# SCH_HV-Switch_2025-05-17.net
KiCad netlist of a schematic drawn in EasyEDA
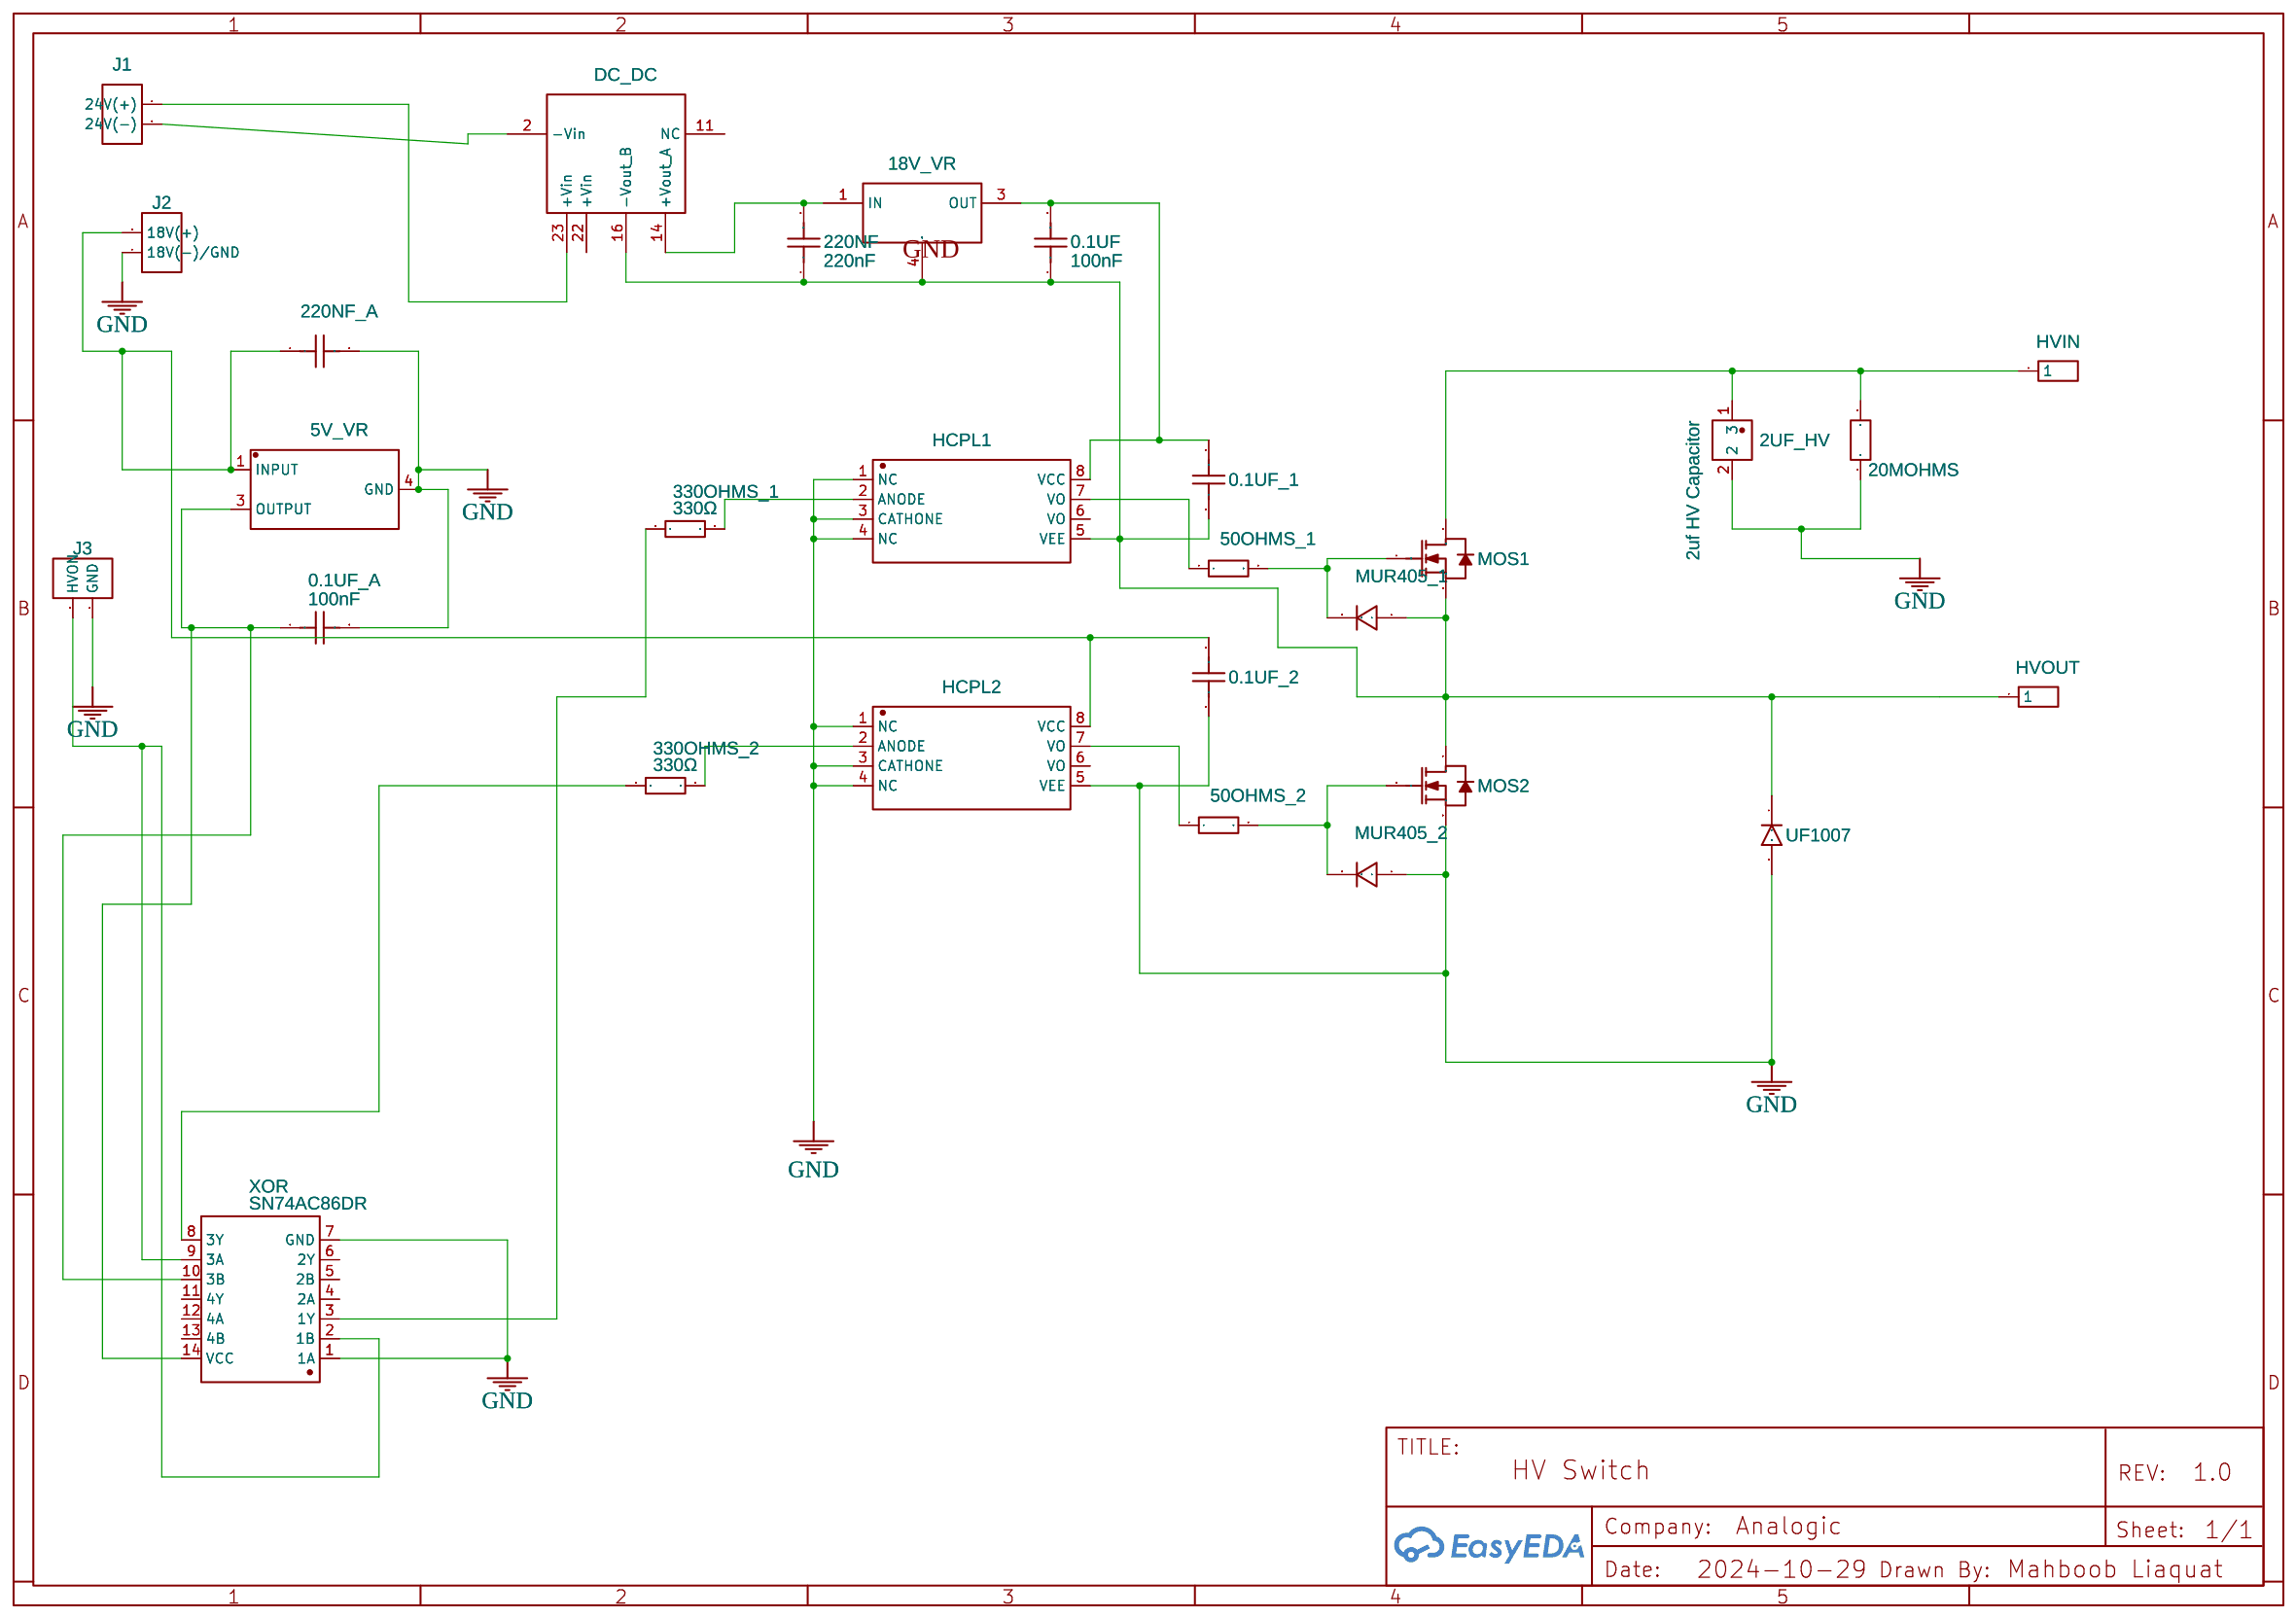
[diagram p0: schematic sheet]

(export (version "E")
  (design (tool "Eeschema 10.0.6"))
  (components
    (comp (ref "0.1UF")
      (value "100nF")
      (fields (field (name "Manufacturer Part") "C2012X7T2E104K125AE") (field (name "Manufacturer") "TDK"))
      (libsource (lib "") (part "C2012X7T2E104K125AE"))
    )
    (comp (ref "0.1UF_1")
      (value "100nF")
      (fields (field (name "Manufacturer Part") "C2012X7T2E104K125AE") (field (name "Manufacturer") "TDK"))
      (libsource (lib "") (part "C2012X7T2E104K125AE_3"))
    )
    (comp (ref "0.1UF_2")
      (value "100nF")
      (fields (field (name "Manufacturer Part") "C2012X7T2E104K125AE") (field (name "Manufacturer") "TDK"))
      (libsource (lib "") (part "C2012X7T2E104K125AE_2"))
    )
    (comp (ref "0.1UF_A")
      (value "100nF")
      (fields (field (name "Manufacturer Part") "C2012X7T2E104K125AE") (field (name "Manufacturer") "TDK"))
      (libsource (lib "") (part "C2012X7T2E104K125AE_1"))
    )
    (comp (ref "2UF_HV") (value "2uf HV Capacitor") (libsource (lib "") (part "2uf HV Capacitor")))
    (comp (ref "5V_VR")
      (value "MC7805BDTG")
      (fields (field (name "Manufacturer") "onsemi(安森美)"))
      (libsource (lib "") (part "MC7805BDTG"))
    )
    (comp (ref "18V_VR")
      (value "MC7818CD2TR4G")
      (fields (field (name "Manufacturer") "onsemi(安森美)"))
      (libsource (lib "") (part "MC7818CD2TR4G"))
    )
    (comp (ref "20MOHMS")
      (value "3.32MΩ")
      (fields
        (field (name "Manufacturer Part") "CRMA2010AF3M32FKEF")
        (field (name "Manufacturer") "VISHAY(威世)")
      )
      (libsource (lib "") (part "CRMA2010AF3M32FKEF"))
    )
    (comp (ref "50OHMS_1")
      (value "49.9Ω")
      (fields (field (name "Manufacturer Part") "RC1206FR-0749R9L") (field (name "Manufacturer") "YAGEO(国巨)"))
      (libsource (lib "") (part "RC1206FR-0749R9L"))
    )
    (comp (ref "50OHMS_2")
      (value "49.9Ω")
      (fields (field (name "Manufacturer Part") "RC1206FR-0749R9L") (field (name "Manufacturer") "YAGEO(国巨)"))
      (libsource (lib "") (part "RC1206FR-0749R9L"))
    )
    (comp (ref "220NF")
      (value "220nF")
      (fields
        (field (name "Manufacturer Part") "CC1206JKX7R9BB224")
        (field (name "Manufacturer") "YAGEO(国巨)")
      )
      (libsource (lib "") (part "CC1206JKX7R9BB224_1"))
    )
    (comp (ref "220NF_A")
      (value "220nF")
      (fields
        (field (name "Manufacturer Part") "CC1206JKX7R9BB224")
        (field (name "Manufacturer") "YAGEO(国巨)")
      )
      (libsource (lib "") (part "CC1206JKX7R9BB224"))
    )
    (comp (ref "330OHMS_1")
      (value "330Ω")
      (fields (field (name "Manufacturer Part") "RC0603JR-07330RL") (field (name "Manufacturer") "YAGEO(国巨)"))
      (libsource (lib "") (part "RC0603JR-07330RL"))
    )
    (comp (ref "330OHMS_2")
      (value "330Ω")
      (fields (field (name "Manufacturer Part") "RC0603JR-07330RL") (field (name "Manufacturer") "YAGEO(国巨)"))
      (libsource (lib "") (part "RC0603JR-07330RL"))
    )
    (comp (ref "DC_DC") (value "DC DC converter") (libsource (lib "") (part "DC DC converter")))
    (comp (ref "HCPL1")
      (value "HCPL-3120-300E")
      (fields (field (name "Manufacturer") "Broadcom/AVAGO(安华高)"))
      (libsource (lib "") (part "HCPL-3120-300E"))
    )
    (comp (ref "HCPL2")
      (value "HCPL-3120-300E")
      (fields (field (name "Manufacturer") "Broadcom/AVAGO(安华高)"))
      (libsource (lib "") (part "HCPL-3120-300E"))
    )
    (comp (ref "HVIN") (value "HVIN") (libsource (lib "") (part "HDR-M-2.54_1x1_1")))
    (comp (ref "HVOUT") (value "HVOUT") (libsource (lib "") (part "HDR-M-2.54_1x1")))
    (comp (ref "J1")
      (value "282836-2")
      (fields (field (name "Manufacturer") "TE-Connectivity"))
      (libsource (lib "") (part "282836-2_1"))
    )
    (comp (ref "J2")
      (value "282836-2")
      (fields (field (name "Manufacturer") "TE-Connectivity"))
      (libsource (lib "") (part "282836-2"))
    )
    (comp (ref "J3")
      (value "282836-2")
      (fields (field (name "Manufacturer") "TE-Connectivity"))
      (libsource (lib "") (part "282836-2_2"))
    )
    (comp (ref "MOS1")
      (value "IXTA1N200P3HV")
      (fields (field (name "Manufacturer") "Littelfuse/IXYS"))
      (libsource (lib "") (part "IXTA1N200P3HV"))
    )
    (comp (ref "MOS2")
      (value "IXTA1N200P3HV")
      (fields (field (name "Manufacturer") "Littelfuse/IXYS"))
      (libsource (lib "") (part "IXTA1N200P3HV"))
    )
    (comp (ref "MUR405_1")
      (value "MURS105T3G")
      (fields (field (name "Manufacturer") "onsemi(安森美)"))
      (libsource (lib "") (part "MURS105T3G"))
    )
    (comp (ref "MUR405_2")
      (value "MURS105T3G")
      (fields (field (name "Manufacturer") "onsemi(安森美)"))
      (libsource (lib "") (part "MURS105T3G"))
    )
    (comp (ref "UF1007")
      (value "US1M-13-F")
      (fields (field (name "Manufacturer") "DIODES(美台)"))
      (libsource (lib "") (part "US1M-13-F"))
    )
    (comp (ref "XOR")
      (value "SN74AC86DR")
      (fields (field (name "Manufacturer") "TI(德州仪器)"))
      (libsource (lib "") (part "SN74AC86DR"))
    )
  )
  (nets
    (net (code "1") (name "GND") (class "Default")
      (node (ref "0.1UF_2") (pin "1") (pinfunction "1_1") (pintype "unspecified"))
      (node (ref "0.1UF_A") (pin "2") (pinfunction "2_2") (pintype "unspecified"))
      (node (ref "20MOHMS") (pin "1") (pinfunction "1_1") (pintype "unspecified"))
      (node (ref "220NF_A") (pin "2") (pinfunction "2_2") (pintype "unspecified"))
      (node (ref "2UF_HV") (pin "2") (pinfunction "2_2") (pintype "unspecified"))
      (node (ref "5V_VR") (pin "4") (pinfunction "GND_4") (pintype "unspecified"))
      (node (ref "HCPL1") (pin "1") (pinfunction "NC_1") (pintype "unspecified"))
      (node (ref "HCPL1") (pin "3") (pinfunction "CATHONE_3") (pintype "unspecified"))
      (node (ref "HCPL1") (pin "4") (pinfunction "NC_4") (pintype "unspecified"))
      (node (ref "HCPL2") (pin "1") (pinfunction "NC_1") (pintype "unspecified"))
      (node (ref "HCPL2") (pin "3") (pinfunction "CATHONE_3") (pintype "unspecified"))
      (node (ref "HCPL2") (pin "4") (pinfunction "NC_4") (pintype "unspecified"))
      (node (ref "HCPL2") (pin "5") (pinfunction "VEE_5") (pintype "unspecified"))
      (node (ref "J2") (pin "1") (pinfunction "18V(-)/GND_1") (pintype "unspecified"))
      (node (ref "J3") (pin "1") (pinfunction "GND_1") (pintype "unspecified"))
      (node (ref "MOS2") (pin "3") (pinfunction "S_3") (pintype "unspecified"))
      (node (ref "MUR405_2") (pin "1") (pinfunction "1_1") (pintype "unspecified"))
      (node (ref "UF1007") (pin "2") (pinfunction "2_2") (pintype "unspecified"))
      (node (ref "XOR") (pin "1") (pinfunction "1A_1") (pintype "unspecified"))
      (node (ref "XOR") (pin "7") (pinfunction "GND_7") (pintype "unspecified"))
    )
    (net (code "2") (name "Net-(2UF_HV-3)") (class "Default")
      (node (ref "20MOHMS") (pin "2") (pinfunction "2_2") (pintype "unspecified"))
      (node (ref "2UF_HV") (pin "1") (pinfunction "3_1") (pintype "unspecified"))
      (node (ref "HVIN") (pin "1") (pinfunction "1_1") (pintype "input"))
      (node (ref "MOS1") (pin "2") (pinfunction "D_2") (pintype "unspecified"))
    )
    (net (code "3") (name "Net-(5V_VR-INPUT)") (class "Default")
      (node (ref "0.1UF_2") (pin "2") (pinfunction "2_2") (pintype "unspecified"))
      (node (ref "220NF_A") (pin "1") (pinfunction "1_1") (pintype "unspecified"))
      (node (ref "5V_VR") (pin "1") (pinfunction "INPUT_1") (pintype "unspecified"))
      (node (ref "HCPL2") (pin "8") (pinfunction "VCC_8") (pintype "unspecified"))
      (node (ref "J2") (pin "2") (pinfunction "18V(+)_2") (pintype "unspecified"))
    )
    (net (code "4") (name "Net-(5V_VR-OUTPUT)") (class "Default")
      (node (ref "0.1UF_A") (pin "1") (pinfunction "1_1") (pintype "unspecified"))
      (node (ref "5V_VR") (pin "3") (pinfunction "OUTPUT_3") (pintype "unspecified"))
      (node (ref "XOR") (pin "10") (pinfunction "3B_10") (pintype "unspecified"))
      (node (ref "XOR") (pin "14") (pinfunction "VCC_14") (pintype "unspecified"))
    )
    (net (code "5") (name "Net-(18V_VR-GND)") (class "Default")
      (node (ref "0.1UF") (pin "1") (pinfunction "1_1") (pintype "unspecified"))
      (node (ref "0.1UF_1") (pin "2") (pinfunction "2_2") (pintype "unspecified"))
      (node (ref "18V_VR") (pin "4") (pinfunction "GND_4") (pintype "passive"))
      (node (ref "220NF") (pin "1") (pinfunction "1_1") (pintype "unspecified"))
      (node (ref "DC_DC") (pin "16") (pinfunction "-Vout_B_16") (pintype "unspecified"))
      (node (ref "HCPL1") (pin "5") (pinfunction "VEE_5") (pintype "unspecified"))
      (node (ref "HVOUT") (pin "1") (pinfunction "1_1") (pintype "input"))
      (node (ref "MOS1") (pin "3") (pinfunction "S_3") (pintype "unspecified"))
      (node (ref "MOS2") (pin "2") (pinfunction "D_2") (pintype "unspecified"))
      (node (ref "MUR405_1") (pin "1") (pinfunction "1_1") (pintype "unspecified"))
      (node (ref "UF1007") (pin "1") (pinfunction "1_1") (pintype "unspecified"))
    )
    (net (code "6") (name "Net-(18V_VR-IN)") (class "Default")
      (node (ref "18V_VR") (pin "1") (pinfunction "IN_1") (pintype "passive"))
      (node (ref "220NF") (pin "2") (pinfunction "2_2") (pintype "unspecified"))
      (node (ref "DC_DC") (pin "14") (pinfunction "+Vout_A_14") (pintype "unspecified"))
    )
    (net (code "7") (name "Net-(18V_VR-OUT)") (class "Default")
      (node (ref "0.1UF") (pin "2") (pinfunction "2_2") (pintype "unspecified"))
      (node (ref "0.1UF_1") (pin "1") (pinfunction "1_1") (pintype "unspecified"))
      (node (ref "18V_VR") (pin "3") (pinfunction "OUT_3") (pintype "passive"))
      (node (ref "HCPL1") (pin "8") (pinfunction "VCC_8") (pintype "unspecified"))
    )
    (net (code "8") (name "Net-(50OHMS_1-Pad1)") (class "Default")
      (node (ref "50OHMS_1") (pin "1") (pinfunction "1_1") (pintype "unspecified"))
      (node (ref "HCPL1") (pin "7") (pinfunction "VO_7") (pintype "unspecified"))
    )
    (net (code "9") (name "Net-(50OHMS_2-Pad1)") (class "Default")
      (node (ref "50OHMS_2") (pin "1") (pinfunction "1_1") (pintype "unspecified"))
      (node (ref "HCPL2") (pin "7") (pinfunction "VO_7") (pintype "unspecified"))
    )
    (net (code "10") (name "Net-(DC_DC--Vin)") (class "Default")
      (node (ref "DC_DC") (pin "2") (pinfunction "-Vin_2") (pintype "unspecified"))
      (node (ref "J1") (pin "2") (pinfunction "24V(-)_2") (pintype "unspecified"))
    )
    (net (code "11") (name "Net-(HCPL1-ANODE)") (class "Default")
      (node (ref "330OHMS_1") (pin "2") (pinfunction "2_2") (pintype "input"))
      (node (ref "HCPL1") (pin "2") (pinfunction "ANODE_2") (pintype "unspecified"))
    )
    (net (code "12") (name "Net-(HCPL2-ANODE)") (class "Default")
      (node (ref "330OHMS_2") (pin "2") (pinfunction "2_2") (pintype "input"))
      (node (ref "HCPL2") (pin "2") (pinfunction "ANODE_2") (pintype "unspecified"))
    )
    (net (code "13") (name "Net-(J1-24V(+))") (class "Default")
      (node (ref "DC_DC") (pin "23") (pinfunction "+Vin_23") (pintype "unspecified"))
      (node (ref "J1") (pin "1") (pinfunction "24V(+)_1") (pintype "unspecified"))
    )
    (net (code "14") (name "Net-(J3-HVON)") (class "Default")
      (node (ref "J3") (pin "2") (pinfunction "HVON_2") (pintype "unspecified"))
      (node (ref "XOR") (pin "2") (pinfunction "1B_2") (pintype "unspecified"))
      (node (ref "XOR") (pin "9") (pinfunction "3A_9") (pintype "unspecified"))
    )
    (net (code "15") (name "Net-(MOS1-G)") (class "Default")
      (node (ref "50OHMS_1") (pin "2") (pinfunction "2_2") (pintype "unspecified"))
      (node (ref "MOS1") (pin "1") (pinfunction "G_1") (pintype "unspecified"))
      (node (ref "MUR405_1") (pin "2") (pinfunction "2_2") (pintype "unspecified"))
    )
    (net (code "16") (name "Net-(MOS2-G)") (class "Default")
      (node (ref "50OHMS_2") (pin "2") (pinfunction "2_2") (pintype "unspecified"))
      (node (ref "MOS2") (pin "1") (pinfunction "G_1") (pintype "unspecified"))
      (node (ref "MUR405_2") (pin "2") (pinfunction "2_2") (pintype "unspecified"))
    )
    (net (code "17") (name "Net-(XOR-1Y)") (class "Default")
      (node (ref "330OHMS_1") (pin "1") (pinfunction "1_1") (pintype "input"))
      (node (ref "XOR") (pin "3") (pinfunction "1Y_3") (pintype "unspecified"))
    )
    (net (code "18") (name "Net-(XOR-3Y)") (class "Default")
      (node (ref "330OHMS_2") (pin "1") (pinfunction "1_1") (pintype "input"))
      (node (ref "XOR") (pin "8") (pinfunction "3Y_8") (pintype "unspecified"))
    )
    (net (code "19") (name "unconnected-(DC_DC-+Vin-Pad22)") (class "Default")
      (node (ref "DC_DC") (pin "22") (pinfunction "+Vin_22") (pintype "unspecified"))
    )
    (net (code "20") (name "unconnected-(DC_DC-NC-Pad11)") (class "Default")
      (node (ref "DC_DC") (pin "11") (pinfunction "NC_11") (pintype "unspecified"))
    )
    (net (code "21") (name "unconnected-(HCPL1-VO-Pad6)") (class "Default")
      (node (ref "HCPL1") (pin "6") (pinfunction "VO_6") (pintype "unspecified"))
    )
    (net (code "22") (name "unconnected-(HCPL2-VO-Pad6)") (class "Default")
      (node (ref "HCPL2") (pin "6") (pinfunction "VO_6") (pintype "unspecified"))
    )
    (net (code "23") (name "unconnected-(XOR-2A-Pad4)") (class "Default")
      (node (ref "XOR") (pin "4") (pinfunction "2A_4") (pintype "unspecified"))
    )
    (net (code "24") (name "unconnected-(XOR-2B-Pad5)") (class "Default")
      (node (ref "XOR") (pin "5") (pinfunction "2B_5") (pintype "unspecified"))
    )
    (net (code "25") (name "unconnected-(XOR-2Y-Pad6)") (class "Default")
      (node (ref "XOR") (pin "6") (pinfunction "2Y_6") (pintype "unspecified"))
    )
    (net (code "26") (name "unconnected-(XOR-4A-Pad12)") (class "Default")
      (node (ref "XOR") (pin "12") (pinfunction "4A_12") (pintype "unspecified"))
    )
    (net (code "27") (name "unconnected-(XOR-4B-Pad13)") (class "Default")
      (node (ref "XOR") (pin "13") (pinfunction "4B_13") (pintype "unspecified"))
    )
    (net (code "28") (name "unconnected-(XOR-4Y-Pad11)") (class "Default")
      (node (ref "XOR") (pin "11") (pinfunction "4Y_11") (pintype "unspecified"))
    )
  )
)
